# EasyEDA_UNO_SHIELD_V1_Schematic.net
KiCad netlist of a schematic drawn in EasyEDA
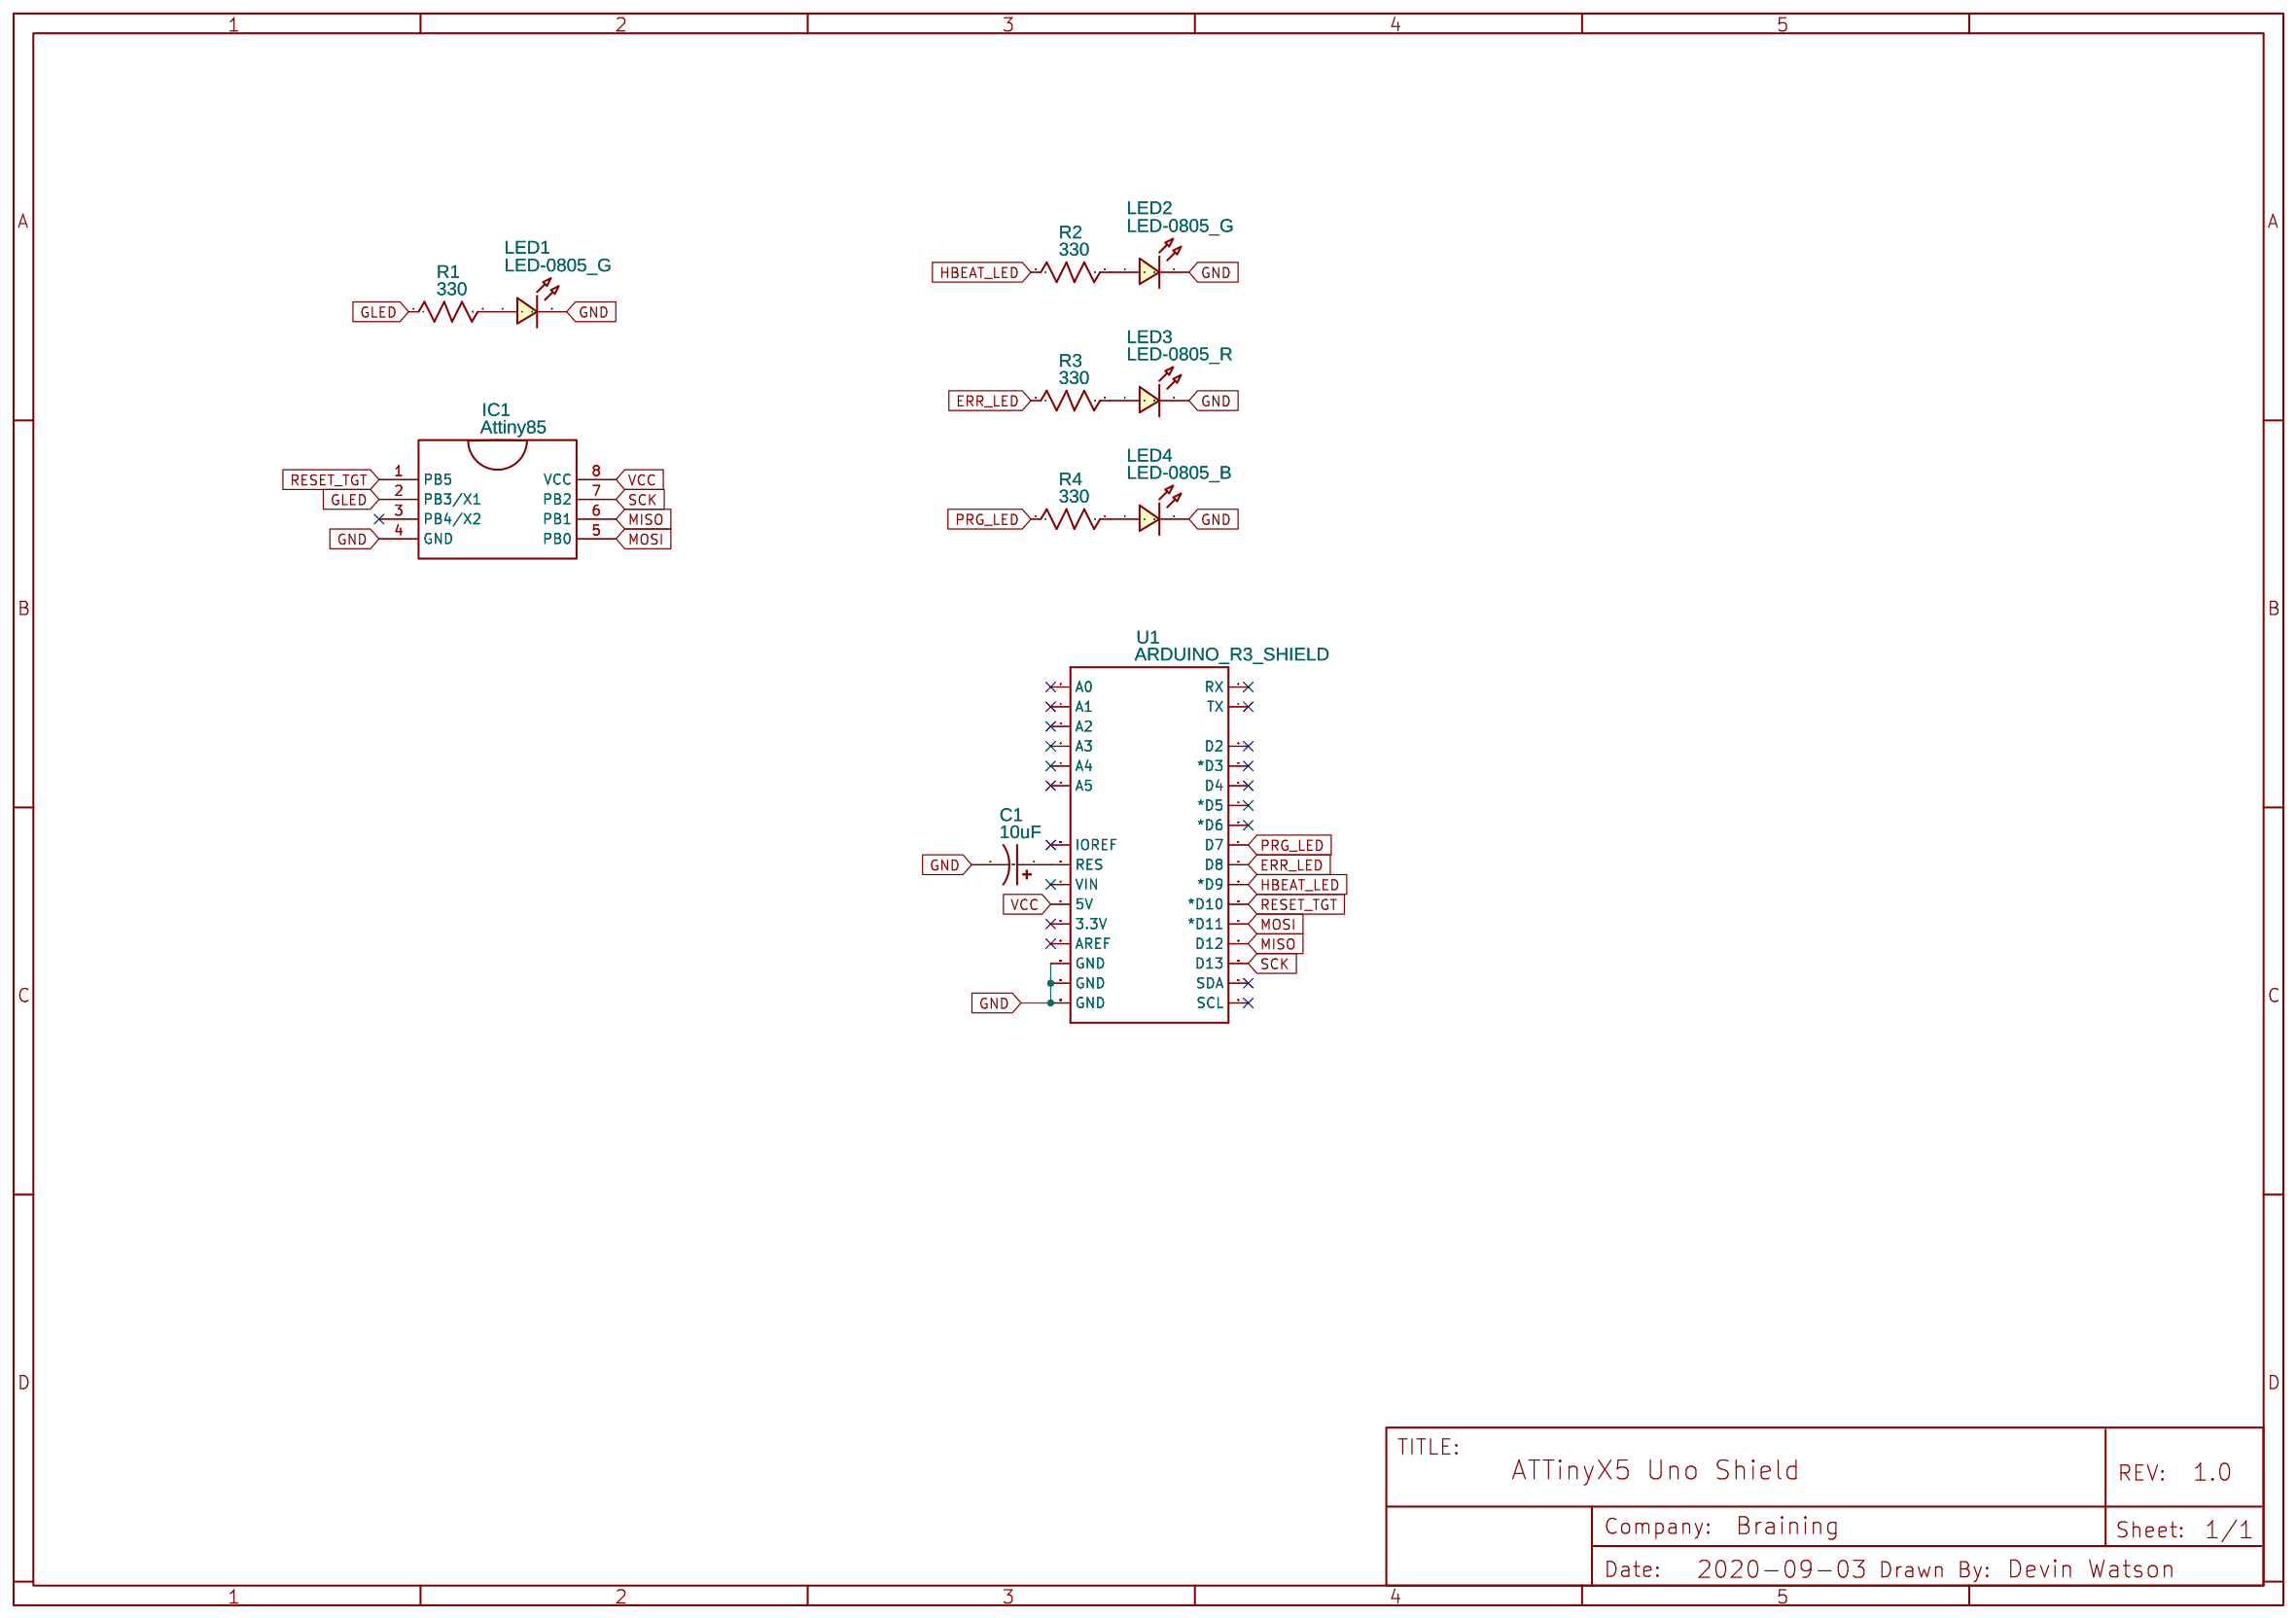
[diagram p0: schematic sheet]

(export (version "E")
  (design (tool "Eeschema 10.0.6"))
  (components
    (comp (ref "C1")
      (value "10uF")
      (fields
        (field (name "BOM_Manufacturer Part") "EEE-HP0J100R")
        (field (name "BOM_Supplier Part") "667-EEE-HP0J100R")
      )
      (libsource (lib "") (part "CE_SMD_D4.0×H5.5_US"))
    )
    (comp (ref "IC1") (value "Attiny85") (libsource (lib "") (part "Attiny85")))
    (comp (ref "LED1")
      (value "LED-0805_G")
      (fields
        (field (name "BOM_Manufacturer Part") "17-21SYGC/S530-E2/TR8")
        (field (name "BOM_Supplier Part") "638-1721SYGCS530E2")
      )
      (libsource (lib "") (part "LED-0805_G"))
    )
    (comp (ref "LED2")
      (value "LED-0805_G")
      (fields
        (field (name "BOM_Manufacturer Part") "17-21SYGC/S530-E2/TR8")
        (field (name "BOM_Supplier Part") "638-1721SYGCS530E2")
      )
      (libsource (lib "") (part "LED-0805_G"))
    )
    (comp (ref "LED3")
      (value "LED-0805_R")
      (fields
        (field (name "BOM_Manufacturer Part") "EL-12-215SURC/S530-A2/TR8")
        (field (name "BOM_Supplier Part") "638-215SURCS530A28")
      )
      (libsource (lib "") (part "LED-0805_R"))
    )
    (comp (ref "LED4")
      (value "LED-0805_B")
      (fields
        (field (name "BOM_Manufacturer Part") "LTST-C170TBKT")
        (field (name "BOM_Supplier Part") "859-LTST-C170TBKT")
      )
      (libsource (lib "") (part "LED-0805_B"))
    )
    (comp (ref "R1")
      (value "330")
      (fields
        (field (name "BOM_Manufacturer Part") "CRCW0805330RJNEAC")
        (field (name "BOM_Supplier Part") "71-CRCW0805330RJNEAC")
      )
      (libsource (lib "") (part "R_0805_US"))
    )
    (comp (ref "R2")
      (value "330")
      (fields
        (field (name "BOM_Manufacturer Part") "CRCW0805330RJNEAC")
        (field (name "BOM_Supplier Part") "71-CRCW0805330RJNEAC")
      )
      (libsource (lib "") (part "R_0805_US"))
    )
    (comp (ref "R3")
      (value "330")
      (fields
        (field (name "BOM_Manufacturer Part") "CRCW0805330RJNEAC")
        (field (name "BOM_Supplier Part") "71-CRCW0805330RJNEAC")
      )
      (libsource (lib "") (part "R_0805_US"))
    )
    (comp (ref "R4")
      (value "330")
      (fields
        (field (name "BOM_Manufacturer Part") "CRCW0805330RJNEAC")
        (field (name "BOM_Supplier Part") "71-CRCW0805330RJNEAC")
      )
      (libsource (lib "") (part "R_0805_US"))
    )
    (comp (ref "U1") (value "ARDUINO_R3_SHIELD") (libsource (lib "") (part "ARDUINO_R3_SHIELD")))
  )
  (nets
    (net (code "1") (name "ERR_LED") (class "Default")
      (node (ref "R3") (pin "1") (pinfunction "1_1") (pintype "unspecified"))
      (node (ref "U1") (pin "D8") (pinfunction "D8_D8") (pintype "unspecified"))
    )
    (net (code "2") (name "GLED") (class "Default")
      (node (ref "IC1") (pin "2") (pinfunction "PB3/X1_2") (pintype "bidirectional"))
      (node (ref "R1") (pin "1") (pinfunction "1_1") (pintype "unspecified"))
    )
    (net (code "3") (name "GND") (class "Default")
      (node (ref "C1") (pin "2") (pinfunction "2_2") (pintype "unspecified"))
      (node (ref "IC1") (pin "4") (pinfunction "GND_4") (pintype "passive"))
      (node (ref "LED1") (pin "2") (pinfunction "2_2") (pintype "unspecified"))
      (node (ref "LED2") (pin "2") (pinfunction "2_2") (pintype "unspecified"))
      (node (ref "LED3") (pin "2") (pinfunction "2_2") (pintype "unspecified"))
      (node (ref "LED4") (pin "2") (pinfunction "2_2") (pintype "unspecified"))
      (node (ref "U1") (pin "GND@0") (pinfunction "GND_GND@0") (pintype "unspecified"))
      (node (ref "U1") (pin "GND@1") (pinfunction "GND_GND@1") (pintype "unspecified"))
      (node (ref "U1") (pin "GND@2") (pinfunction "GND_GND@2") (pintype "unspecified"))
    )
    (net (code "4") (name "HBEAT_LED") (class "Default")
      (node (ref "R2") (pin "1") (pinfunction "1_1") (pintype "unspecified"))
      (node (ref "U1") (pin "D9") (pinfunction "*D9_D9") (pintype "unspecified"))
    )
    (net (code "5") (name "MISO") (class "Default")
      (node (ref "IC1") (pin "6") (pinfunction "PB1_6") (pintype "bidirectional"))
      (node (ref "U1") (pin "D12") (pinfunction "D12_D12") (pintype "unspecified"))
    )
    (net (code "6") (name "MOSI") (class "Default")
      (node (ref "IC1") (pin "5") (pinfunction "PB0_5") (pintype "bidirectional"))
      (node (ref "U1") (pin "D11") (pinfunction "*D11_D11") (pintype "unspecified"))
    )
    (net (code "7") (name "Net-(C1-Pad1)") (class "Default")
      (node (ref "C1") (pin "1") (pinfunction "1_1") (pintype "unspecified"))
      (node (ref "U1") (pin "RES") (pinfunction "RES_RES") (pintype "unspecified"))
    )
    (net (code "8") (name "Net-(LED1-Pad1)") (class "Default")
      (node (ref "LED1") (pin "1") (pinfunction "1_1") (pintype "unspecified"))
      (node (ref "R1") (pin "2") (pinfunction "2_2") (pintype "unspecified"))
    )
    (net (code "9") (name "Net-(LED2-Pad1)") (class "Default")
      (node (ref "LED2") (pin "1") (pinfunction "1_1") (pintype "unspecified"))
      (node (ref "R2") (pin "2") (pinfunction "2_2") (pintype "unspecified"))
    )
    (net (code "10") (name "Net-(LED3-Pad1)") (class "Default")
      (node (ref "LED3") (pin "1") (pinfunction "1_1") (pintype "unspecified"))
      (node (ref "R3") (pin "2") (pinfunction "2_2") (pintype "unspecified"))
    )
    (net (code "11") (name "Net-(LED4-Pad1)") (class "Default")
      (node (ref "LED4") (pin "1") (pinfunction "1_1") (pintype "unspecified"))
      (node (ref "R4") (pin "2") (pinfunction "2_2") (pintype "unspecified"))
    )
    (net (code "12") (name "PRG_LED") (class "Default")
      (node (ref "R4") (pin "1") (pinfunction "1_1") (pintype "unspecified"))
      (node (ref "U1") (pin "D7") (pinfunction "D7_D7") (pintype "unspecified"))
    )
    (net (code "13") (name "RESET_TGT") (class "Default")
      (node (ref "IC1") (pin "1") (pinfunction "PB5_1") (pintype "bidirectional"))
      (node (ref "U1") (pin "D10") (pinfunction "*D10_D10") (pintype "unspecified"))
    )
    (net (code "14") (name "SCK") (class "Default")
      (node (ref "IC1") (pin "7") (pinfunction "PB2_7") (pintype "bidirectional"))
      (node (ref "U1") (pin "D13") (pinfunction "D13_D13") (pintype "unspecified"))
    )
    (net (code "15") (name "VCC") (class "Default")
      (node (ref "IC1") (pin "8") (pinfunction "VCC_8") (pintype "passive"))
      (node (ref "U1") (pin "5V") (pinfunction "5V_5V") (pintype "unspecified"))
    )
    (net (code "16") (name "unconnected-(IC1-PB4{slash}X2-Pad3)") (class "Default")
      (node (ref "IC1") (pin "3") (pinfunction "PB4/X2_3") (pintype "bidirectional+no_connect"))
    )
    (net (code "17") (name "unconnected-(U1-*D3-PadD3)") (class "Default")
      (node (ref "U1") (pin "D3") (pinfunction "*D3_D3") (pintype "unspecified+no_connect"))
    )
    (net (code "18") (name "unconnected-(U1-*D5-PadD5)") (class "Default")
      (node (ref "U1") (pin "D5") (pinfunction "*D5_D5") (pintype "unspecified+no_connect"))
    )
    (net (code "19") (name "unconnected-(U1-*D6-PadD6)") (class "Default")
      (node (ref "U1") (pin "D6") (pinfunction "*D6_D6") (pintype "unspecified+no_connect"))
    )
    (net (code "20") (name "unconnected-(U1-Pad3.3V)") (class "Default")
      (node (ref "U1") (pin "3.3V") (pinfunction "3.3V_3.3V") (pintype "unspecified+no_connect"))
    )
    (net (code "21") (name "unconnected-(U1-PadA0)") (class "Default")
      (node (ref "U1") (pin "A0") (pinfunction "A0_A0") (pintype "unspecified+no_connect"))
    )
    (net (code "22") (name "unconnected-(U1-PadA1)") (class "Default")
      (node (ref "U1") (pin "A1") (pinfunction "A1_A1") (pintype "unspecified+no_connect"))
    )
    (net (code "23") (name "unconnected-(U1-PadA2)") (class "Default")
      (node (ref "U1") (pin "A2") (pinfunction "A2_A2") (pintype "unspecified+no_connect"))
    )
    (net (code "24") (name "unconnected-(U1-PadA3)") (class "Default")
      (node (ref "U1") (pin "A3") (pinfunction "A3_A3") (pintype "unspecified+no_connect"))
    )
    (net (code "25") (name "unconnected-(U1-PadA4)") (class "Default")
      (node (ref "U1") (pin "A4") (pinfunction "A4_A4") (pintype "unspecified+no_connect"))
    )
    (net (code "26") (name "unconnected-(U1-PadA5)") (class "Default")
      (node (ref "U1") (pin "A5") (pinfunction "A5_A5") (pintype "unspecified+no_connect"))
    )
    (net (code "27") (name "unconnected-(U1-PadAREF)") (class "Default")
      (node (ref "U1") (pin "AREF") (pinfunction "AREF_AREF") (pintype "unspecified+no_connect"))
    )
    (net (code "28") (name "unconnected-(U1-PadD2)") (class "Default")
      (node (ref "U1") (pin "D2") (pinfunction "D2_D2") (pintype "unspecified+no_connect"))
    )
    (net (code "29") (name "unconnected-(U1-PadD4)") (class "Default")
      (node (ref "U1") (pin "D4") (pinfunction "D4_D4") (pintype "unspecified+no_connect"))
    )
    (net (code "30") (name "unconnected-(U1-PadIOREF)") (class "Default")
      (node (ref "U1") (pin "IOREF") (pinfunction "IOREF_IOREF") (pintype "unspecified+no_connect"))
    )
    (net (code "31") (name "unconnected-(U1-PadRX)") (class "Default")
      (node (ref "U1") (pin "RX") (pinfunction "RX_RX") (pintype "unspecified+no_connect"))
    )
    (net (code "32") (name "unconnected-(U1-PadSCL)") (class "Default")
      (node (ref "U1") (pin "SCL") (pinfunction "SCL_SCL") (pintype "unspecified+no_connect"))
    )
    (net (code "33") (name "unconnected-(U1-PadSDA)") (class "Default")
      (node (ref "U1") (pin "SDA") (pinfunction "SDA_SDA") (pintype "unspecified+no_connect"))
    )
    (net (code "34") (name "unconnected-(U1-PadTX)") (class "Default")
      (node (ref "U1") (pin "TX") (pinfunction "TX_TX") (pintype "unspecified+no_connect"))
    )
    (net (code "35") (name "unconnected-(U1-PadVIN)") (class "Default")
      (node (ref "U1") (pin "VIN") (pinfunction "VIN_VIN") (pintype "unspecified+no_connect"))
    )
  )
)
